# CS_16f1827.net
KiCad netlist of a schematic drawn in EAGLE
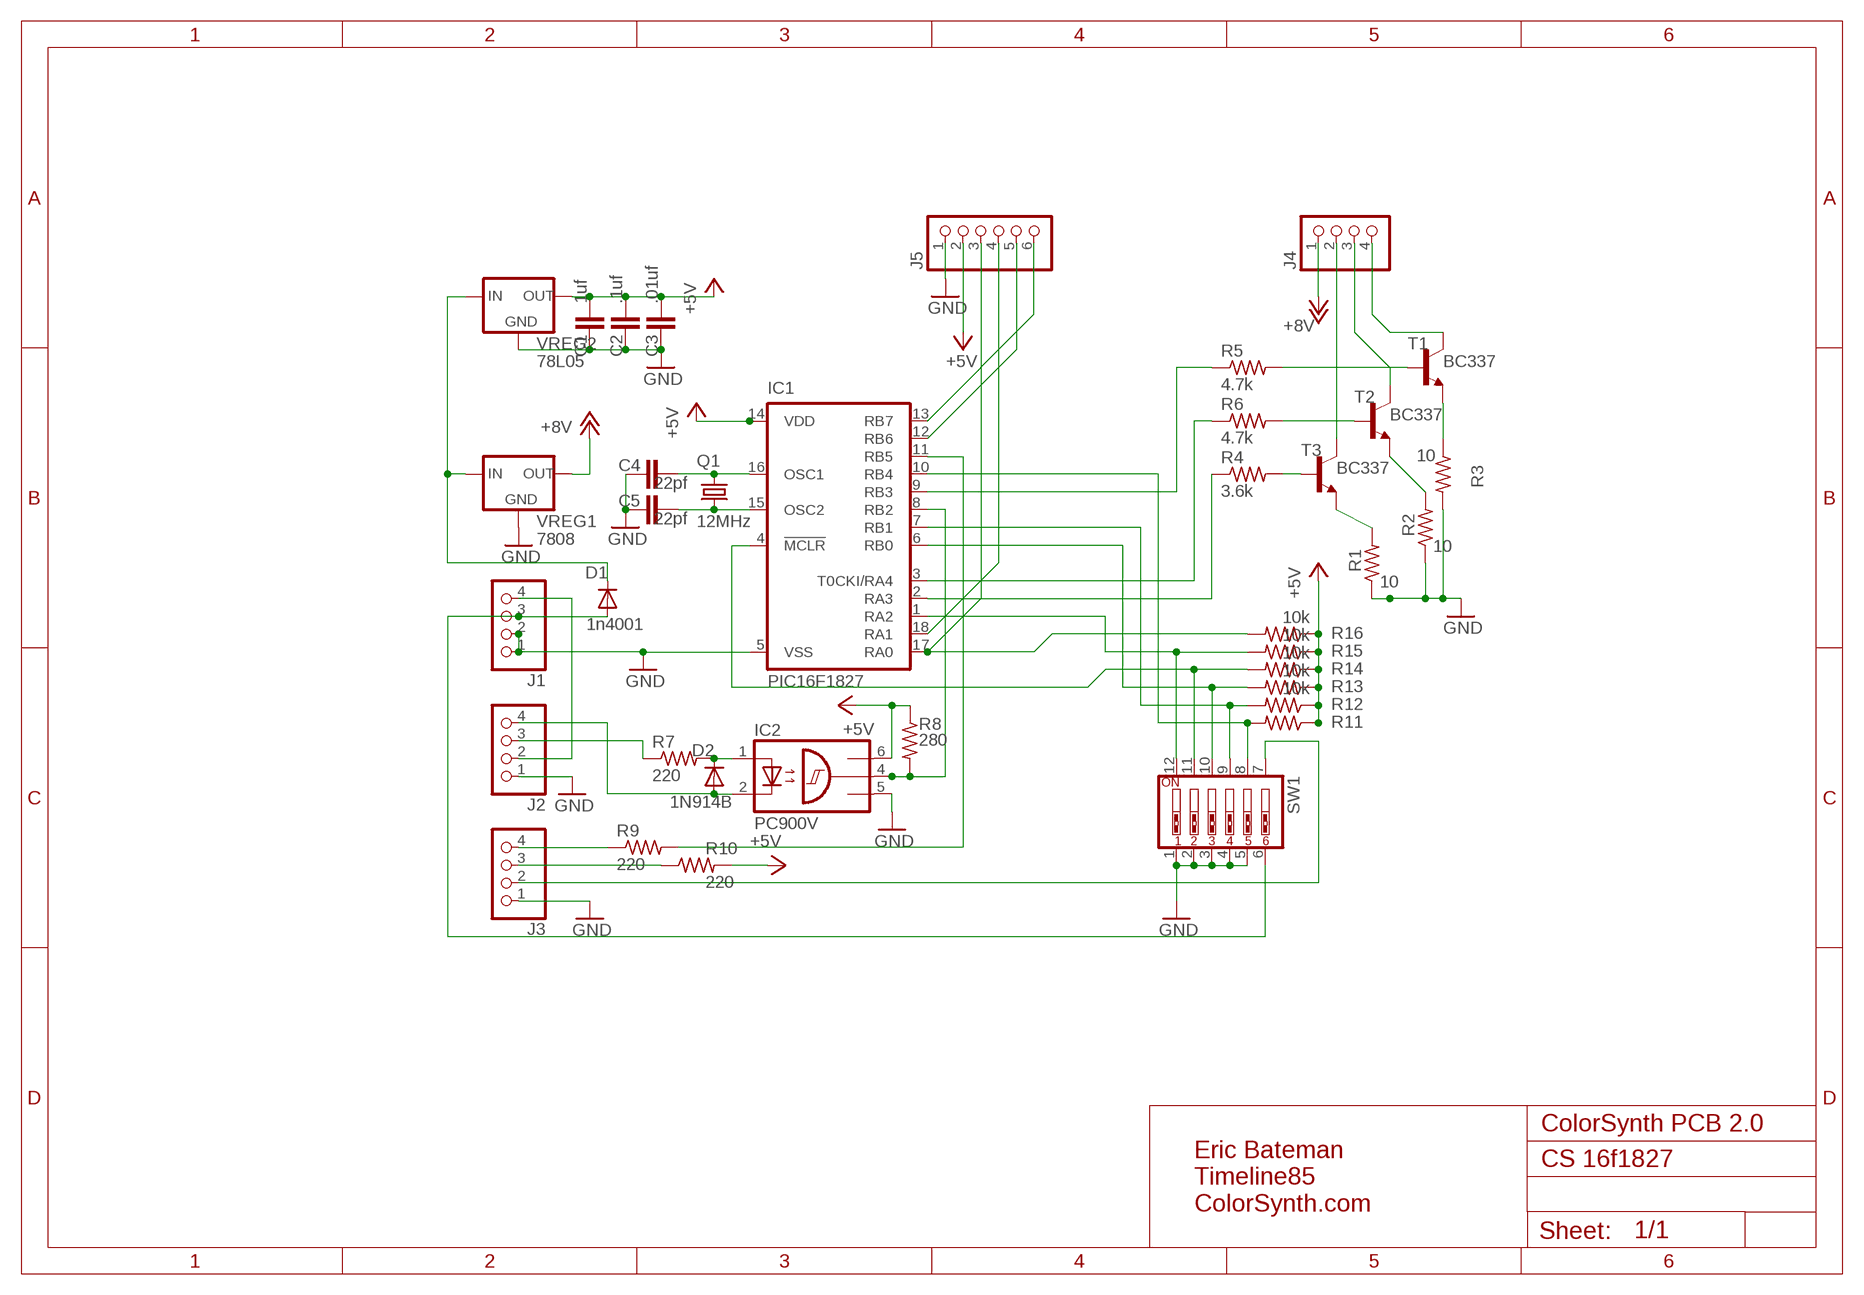
[diagram p0: schematic, sheet 1]

(export (version "E")
  (design (tool "Eeschema 10.0.6"))
  (components
    (comp (ref "C1")
      (value "1uf")
      (footprint "eagle-import:C5B3.5")
      (libsource (lib "eagle-import") (part "C5/3.5"))
    )
    (comp (ref "C2")
      (value ".1uf")
      (footprint "eagle-import:C5B3.5")
      (libsource (lib "eagle-import") (part "C5/3.5"))
    )
    (comp (ref "C3")
      (value ".01uf")
      (footprint "eagle-import:C5B3.5")
      (libsource (lib "eagle-import") (part "C5/3.5"))
    )
    (comp (ref "C4")
      (value "22pf")
      (footprint "eagle-import:C5B3.5")
      (libsource (lib "eagle-import") (part "C5/3.5"))
    )
    (comp (ref "C5")
      (value "22pf")
      (footprint "eagle-import:C5B3.5")
      (libsource (lib "eagle-import") (part "C5/3.5"))
    )
    (comp (ref "D1")
      (value "1n4001")
      (footprint "eagle-import:DO35-10")
      (libsource (lib "eagle-import") (part "1N4148DO35-10"))
    )
    (comp (ref "D2")
      (value "1N914B")
      (footprint "eagle-import:DO34-7")
      (libsource (lib "eagle-import") (part "BAS15"))
    )
    (comp (ref "IC1")
      (value "PIC16F1827")
      (footprint "eagle-import:DIL18")
      (libsource (lib "eagle-import") (part "PIC16F8P3"))
    )
    (comp (ref "IC2")
      (value "PC900V")
      (footprint "eagle-import:DIL06")
      (libsource (lib "eagle-import") (part "OPI8013"))
    )
    (comp (ref "J1")
      (value "PINHD-1X4")
      (footprint "eagle-import:1X04")
      (libsource (lib "eagle-import") (part "PINHD-1X4"))
    )
    (comp (ref "J2")
      (value "PINHD-1X4")
      (footprint "eagle-import:1X04")
      (libsource (lib "eagle-import") (part "PINHD-1X4"))
    )
    (comp (ref "J3")
      (value "PINHD-1X4")
      (footprint "eagle-import:1X04")
      (libsource (lib "eagle-import") (part "PINHD-1X4"))
    )
    (comp (ref "J4")
      (value "PINHD-1X4")
      (footprint "eagle-import:1X04")
      (libsource (lib "eagle-import") (part "PINHD-1X4"))
    )
    (comp (ref "J5")
      (value "PINHD-1X6")
      (footprint "eagle-import:1X06")
      (libsource (lib "eagle-import") (part "PINHD-1X6"))
    )
    (comp (ref "Q1")
      (value "12MHz")
      (footprint "eagle-import:HC49_S")
      (libsource (lib "eagle-import") (part "CRYSTALHC49S"))
    )
    (comp (ref "R1")
      (value "10")
      (footprint "eagle-import:0617V")
      (libsource (lib "eagle-import") (part "R-US_0617/5V"))
    )
    (comp (ref "R2")
      (value "10")
      (footprint "eagle-import:0617V")
      (libsource (lib "eagle-import") (part "R-US_0617/5V"))
    )
    (comp (ref "R3")
      (value "10")
      (footprint "eagle-import:0617V")
      (libsource (lib "eagle-import") (part "R-US_0617/5V"))
    )
    (comp (ref "R4")
      (value "3.6k")
      (footprint "eagle-import:0207_10")
      (libsource (lib "eagle-import") (part "R-US_0207/10"))
    )
    (comp (ref "R5")
      (value "4.7k")
      (footprint "eagle-import:0207_10")
      (libsource (lib "eagle-import") (part "R-US_0207/10"))
    )
    (comp (ref "R6")
      (value "4.7k")
      (footprint "eagle-import:0207_10")
      (libsource (lib "eagle-import") (part "R-US_0207/10"))
    )
    (comp (ref "R7")
      (value "220")
      (footprint "eagle-import:0207_10")
      (libsource (lib "eagle-import") (part "R-US_0207/10"))
    )
    (comp (ref "R8")
      (value "280")
      (footprint "eagle-import:0207_10")
      (libsource (lib "eagle-import") (part "R-US_0207/10"))
    )
    (comp (ref "R9")
      (value "220")
      (footprint "eagle-import:0207_10")
      (libsource (lib "eagle-import") (part "R-US_0207/10"))
    )
    (comp (ref "R10")
      (value "220")
      (footprint "eagle-import:0207_10")
      (libsource (lib "eagle-import") (part "R-US_0207/10"))
    )
    (comp (ref "R11")
      (value "10k")
      (footprint "eagle-import:0207_10")
      (libsource (lib "eagle-import") (part "R-US_0207/10"))
    )
    (comp (ref "R12")
      (value "10k")
      (footprint "eagle-import:0207_10")
      (libsource (lib "eagle-import") (part "R-US_0207/10"))
    )
    (comp (ref "R13")
      (value "10k")
      (footprint "eagle-import:0207_10")
      (libsource (lib "eagle-import") (part "R-US_0207/10"))
    )
    (comp (ref "R14")
      (value "10k")
      (footprint "eagle-import:0207_10")
      (libsource (lib "eagle-import") (part "R-US_0207/10"))
    )
    (comp (ref "R15")
      (value "10k")
      (footprint "eagle-import:0207_10")
      (libsource (lib "eagle-import") (part "R-US_0207/10"))
    )
    (comp (ref "R16")
      (value "10k")
      (footprint "eagle-import:0207_10")
      (libsource (lib "eagle-import") (part "R-US_0207/10"))
    )
    (comp (ref "SW1")
      (value "SW_DIP-6")
      (footprint "eagle-import:EDG-06")
      (libsource (lib "eagle-import") (part "SW_DIP-6"))
    )
    (comp (ref "T1")
      (value "BC337")
      (footprint "eagle-import:TO92-CBE")
      (libsource (lib "eagle-import") (part "BC337"))
    )
    (comp (ref "T2")
      (value "BC337")
      (footprint "eagle-import:TO92-CBE")
      (libsource (lib "eagle-import") (part "BC337"))
    )
    (comp (ref "T3")
      (value "BC337")
      (footprint "eagle-import:TO92-CBE")
      (libsource (lib "eagle-import") (part "BC337"))
    )
    (comp (ref "VREG1")
      (value "7808")
      (footprint "eagle-import:78XXS")
      (libsource (lib "eagle-import") (part "78XXS"))
    )
    (comp (ref "VREG2")
      (value "78L05")
      (footprint "eagle-import:78LXX")
      (libsource (lib "eagle-import") (part "78LXX"))
    )
  )
  (nets
    (net (code "1") (name "+5V") (class "Default")
      (node (ref "C1") (pin "1") (pinfunction "1_1") (pintype "passive"))
      (node (ref "C2") (pin "1") (pinfunction "1_1") (pintype "passive"))
      (node (ref "C3") (pin "1") (pinfunction "1_1") (pintype "passive"))
      (node (ref "IC1") (pin "14") (pinfunction "VDD_14") (pintype "power_in"))
      (node (ref "IC2") (pin "6") (pinfunction "VCC_6") (pintype "passive"))
      (node (ref "J5") (pin "2") (pinfunction "2_2") (pintype "passive"))
      (node (ref "R10") (pin "2") (pinfunction "2_2") (pintype "passive"))
      (node (ref "R11") (pin "1") (pinfunction "1_1") (pintype "passive"))
      (node (ref "R12") (pin "1") (pinfunction "1_1") (pintype "passive"))
      (node (ref "R13") (pin "1") (pinfunction "1_1") (pintype "passive"))
      (node (ref "R14") (pin "1") (pinfunction "1_1") (pintype "passive"))
      (node (ref "R15") (pin "1") (pinfunction "1_1") (pintype "passive"))
      (node (ref "R16") (pin "1") (pinfunction "1_1") (pintype "passive"))
      (node (ref "R8") (pin "1") (pinfunction "1_1") (pintype "passive"))
      (node (ref "VREG2") (pin "OUT") (pinfunction "OUT_OUT") (pintype "passive"))
    )
    (net (code "2") (name "+8V") (class "Default")
      (node (ref "J4") (pin "1") (pinfunction "1_1") (pintype "passive"))
      (node (ref "VREG1") (pin "OUT") (pinfunction "OUT_OUT") (pintype "passive"))
    )
    (net (code "3") (name "GND") (class "Default")
      (node (ref "C1") (pin "2") (pinfunction "2_2") (pintype "passive"))
      (node (ref "C2") (pin "2") (pinfunction "2_2") (pintype "passive"))
      (node (ref "C3") (pin "2") (pinfunction "2_2") (pintype "passive"))
      (node (ref "C4") (pin "2") (pinfunction "2_2") (pintype "passive"))
      (node (ref "C5") (pin "2") (pinfunction "2_2") (pintype "passive"))
      (node (ref "IC1") (pin "5") (pinfunction "VSS_5") (pintype "power_in"))
      (node (ref "IC2") (pin "5") (pinfunction "GND_5") (pintype "passive"))
      (node (ref "J1") (pin "1") (pinfunction "1_1") (pintype "passive"))
      (node (ref "J1") (pin "2") (pinfunction "2_2") (pintype "passive"))
      (node (ref "J2") (pin "1") (pinfunction "1_1") (pintype "passive"))
      (node (ref "J3") (pin "1") (pinfunction "1_1") (pintype "passive"))
      (node (ref "J5") (pin "1") (pinfunction "1_1") (pintype "passive"))
      (node (ref "R1") (pin "1") (pinfunction "1_1") (pintype "passive"))
      (node (ref "R2") (pin "1") (pinfunction "1_1") (pintype "passive"))
      (node (ref "R3") (pin "2") (pinfunction "2_2") (pintype "passive"))
      (node (ref "SW1") (pin "1") (pinfunction "1_1") (pintype "passive"))
      (node (ref "SW1") (pin "2") (pinfunction "2_2") (pintype "passive"))
      (node (ref "SW1") (pin "3") (pinfunction "3_3") (pintype "passive"))
      (node (ref "SW1") (pin "4") (pinfunction "4_4") (pintype "passive"))
      (node (ref "SW1") (pin "5") (pinfunction "5_5") (pintype "passive"))
      (node (ref "VREG1") (pin "GND") (pinfunction "GND_GND") (pintype "input"))
      (node (ref "VREG2") (pin "GND") (pinfunction "GND_GND") (pintype "input"))
    )
    (net (code "4") (name "Net-(D1-PadA)") (class "Default")
      (node (ref "D1") (pin "A") (pinfunction "A_A") (pintype "passive"))
      (node (ref "J1") (pin "3") (pinfunction "3_3") (pintype "passive"))
      (node (ref "SW1") (pin "6") (pinfunction "6_6") (pintype "passive"))
    )
    (net (code "5") (name "Net-(D1-PadC)") (class "Default")
      (node (ref "D1") (pin "C") (pinfunction "C_C") (pintype "passive"))
      (node (ref "VREG1") (pin "IN") (pinfunction "IN_IN") (pintype "input"))
      (node (ref "VREG2") (pin "IN") (pinfunction "IN_IN") (pintype "input"))
    )
    (net (code "6") (name "Net-(IC1-OSC1)") (class "Default")
      (node (ref "C4") (pin "1") (pinfunction "1_1") (pintype "passive"))
      (node (ref "IC1") (pin "16") (pinfunction "OSC1_16") (pintype "input"))
      (node (ref "Q1") (pin "1") (pinfunction "1_1") (pintype "passive"))
    )
    (net (code "7") (name "Net-(IC1-OSC2)") (class "Default")
      (node (ref "C5") (pin "1") (pinfunction "1_1") (pintype "passive"))
      (node (ref "IC1") (pin "15") (pinfunction "OSC2_15") (pintype "output"))
      (node (ref "Q1") (pin "2") (pinfunction "2_2") (pintype "passive"))
    )
    (net (code "8") (name "Net-(IC1-RA0)") (class "Default")
      (node (ref "IC1") (pin "17") (pinfunction "RA0_17") (pintype "bidirectional"))
      (node (ref "J5") (pin "3") (pinfunction "3_3") (pintype "passive"))
      (node (ref "R16") (pin "2") (pinfunction "2_2") (pintype "passive"))
    )
    (net (code "9") (name "Net-(IC1-RA1)") (class "Default")
      (node (ref "IC1") (pin "18") (pinfunction "RA1_18") (pintype "bidirectional"))
      (node (ref "J5") (pin "4") (pinfunction "4_4") (pintype "passive"))
    )
    (net (code "10") (name "Net-(IC1-RA2)") (class "Default")
      (node (ref "IC1") (pin "1") (pinfunction "RA2_1") (pintype "bidirectional"))
      (node (ref "R15") (pin "2") (pinfunction "2_2") (pintype "passive"))
      (node (ref "SW1") (pin "12") (pinfunction "12_12") (pintype "passive"))
    )
    (net (code "11") (name "Net-(IC1-RA3)") (class "Default")
      (node (ref "IC1") (pin "2") (pinfunction "RA3_2") (pintype "bidirectional"))
      (node (ref "R4") (pin "1") (pinfunction "1_1") (pintype "passive"))
    )
    (net (code "12") (name "Net-(IC1-RB0)") (class "Default")
      (node (ref "IC1") (pin "6") (pinfunction "RB0_6") (pintype "bidirectional"))
      (node (ref "R13") (pin "2") (pinfunction "2_2") (pintype "passive"))
      (node (ref "SW1") (pin "10") (pinfunction "10_10") (pintype "passive"))
    )
    (net (code "13") (name "Net-(IC1-RB1)") (class "Default")
      (node (ref "IC1") (pin "7") (pinfunction "RB1_7") (pintype "bidirectional"))
      (node (ref "R12") (pin "2") (pinfunction "2_2") (pintype "passive"))
      (node (ref "SW1") (pin "9") (pinfunction "9_9") (pintype "passive"))
    )
    (net (code "14") (name "Net-(IC1-RB2)") (class "Default")
      (node (ref "IC1") (pin "8") (pinfunction "RB2_8") (pintype "bidirectional"))
      (node (ref "IC2") (pin "4") (pinfunction "OUT_4") (pintype "passive"))
      (node (ref "R8") (pin "2") (pinfunction "2_2") (pintype "passive"))
    )
    (net (code "15") (name "Net-(IC1-RB3)") (class "Default")
      (node (ref "IC1") (pin "9") (pinfunction "RB3_9") (pintype "bidirectional"))
      (node (ref "R5") (pin "1") (pinfunction "1_1") (pintype "passive"))
    )
    (net (code "16") (name "Net-(IC1-RB4)") (class "Default")
      (node (ref "IC1") (pin "10") (pinfunction "RB4_10") (pintype "bidirectional"))
      (node (ref "R11") (pin "2") (pinfunction "2_2") (pintype "passive"))
      (node (ref "SW1") (pin "8") (pinfunction "8_8") (pintype "passive"))
    )
    (net (code "17") (name "Net-(IC1-RB5)") (class "Default")
      (node (ref "IC1") (pin "11") (pinfunction "RB5_11") (pintype "bidirectional"))
      (node (ref "R9") (pin "2") (pinfunction "2_2") (pintype "passive"))
    )
    (net (code "18") (name "Net-(IC1-RB6)") (class "Default")
      (node (ref "IC1") (pin "12") (pinfunction "RB6_12") (pintype "bidirectional"))
      (node (ref "J5") (pin "5") (pinfunction "5_5") (pintype "passive"))
    )
    (net (code "19") (name "Net-(IC1-RB7)") (class "Default")
      (node (ref "IC1") (pin "13") (pinfunction "RB7_13") (pintype "bidirectional"))
      (node (ref "J5") (pin "6") (pinfunction "6_6") (pintype "passive"))
    )
    (net (code "20") (name "Net-(IC1-T0CKI{slash}RA4)") (class "Default")
      (node (ref "IC1") (pin "3") (pinfunction "T0CKI/RA4_3") (pintype "bidirectional"))
      (node (ref "R6") (pin "1") (pinfunction "1_1") (pintype "passive"))
    )
    (net (code "21") (name "Net-(IC1-~{MCLR})") (class "Default")
      (node (ref "IC1") (pin "4") (pinfunction "~{MCLR}_4") (pintype "input"))
      (node (ref "R14") (pin "2") (pinfunction "2_2") (pintype "passive"))
      (node (ref "SW1") (pin "11") (pinfunction "11_11") (pintype "passive"))
    )
    (net (code "22") (name "Net-(IC2-A)") (class "Default")
      (node (ref "D2") (pin "C") (pinfunction "C_C") (pintype "passive"))
      (node (ref "IC2") (pin "1") (pinfunction "A_1") (pintype "passive"))
      (node (ref "R7") (pin "2") (pinfunction "2_2") (pintype "passive"))
    )
    (net (code "23") (name "Net-(IC2-C)") (class "Default")
      (node (ref "D2") (pin "A") (pinfunction "A_A") (pintype "passive"))
      (node (ref "IC2") (pin "2") (pinfunction "C_2") (pintype "passive"))
      (node (ref "J2") (pin "4") (pinfunction "4_4") (pintype "passive"))
    )
    (net (code "24") (name "Net-(J1-Pad4)") (class "Default")
      (node (ref "J1") (pin "4") (pinfunction "4_4") (pintype "passive"))
      (node (ref "J2") (pin "2") (pinfunction "2_2") (pintype "passive"))
    )
    (net (code "25") (name "Net-(J2-Pad3)") (class "Default")
      (node (ref "J2") (pin "3") (pinfunction "3_3") (pintype "passive"))
      (node (ref "R7") (pin "1") (pinfunction "1_1") (pintype "passive"))
    )
    (net (code "26") (name "Net-(J3-Pad2)") (class "Default")
      (node (ref "J3") (pin "2") (pinfunction "2_2") (pintype "passive"))
      (node (ref "SW1") (pin "7") (pinfunction "7_7") (pintype "passive"))
    )
    (net (code "27") (name "Net-(J3-Pad3)") (class "Default")
      (node (ref "J3") (pin "3") (pinfunction "3_3") (pintype "passive"))
      (node (ref "R10") (pin "1") (pinfunction "1_1") (pintype "passive"))
    )
    (net (code "28") (name "Net-(J3-Pad4)") (class "Default")
      (node (ref "J3") (pin "4") (pinfunction "4_4") (pintype "passive"))
      (node (ref "R9") (pin "1") (pinfunction "1_1") (pintype "passive"))
    )
    (net (code "29") (name "Net-(J4-Pad2)") (class "Default")
      (node (ref "J4") (pin "2") (pinfunction "2_2") (pintype "passive"))
      (node (ref "T3") (pin "C") (pinfunction "C_C") (pintype "passive"))
    )
    (net (code "30") (name "Net-(J4-Pad3)") (class "Default")
      (node (ref "J4") (pin "3") (pinfunction "3_3") (pintype "passive"))
      (node (ref "T2") (pin "C") (pinfunction "C_C") (pintype "passive"))
    )
    (net (code "31") (name "Net-(J4-Pad4)") (class "Default")
      (node (ref "J4") (pin "4") (pinfunction "4_4") (pintype "passive"))
      (node (ref "T1") (pin "C") (pinfunction "C_C") (pintype "passive"))
    )
    (net (code "32") (name "Net-(R1-Pad2)") (class "Default")
      (node (ref "R1") (pin "2") (pinfunction "2_2") (pintype "passive"))
      (node (ref "T3") (pin "E") (pinfunction "E_E") (pintype "passive"))
    )
    (net (code "33") (name "Net-(R2-Pad2)") (class "Default")
      (node (ref "R2") (pin "2") (pinfunction "2_2") (pintype "passive"))
      (node (ref "T2") (pin "E") (pinfunction "E_E") (pintype "passive"))
    )
    (net (code "34") (name "Net-(R3-Pad1)") (class "Default")
      (node (ref "R3") (pin "1") (pinfunction "1_1") (pintype "passive"))
      (node (ref "T1") (pin "E") (pinfunction "E_E") (pintype "passive"))
    )
    (net (code "35") (name "Net-(R4-Pad2)") (class "Default")
      (node (ref "R4") (pin "2") (pinfunction "2_2") (pintype "passive"))
      (node (ref "T3") (pin "B") (pinfunction "B_B") (pintype "passive"))
    )
    (net (code "36") (name "Net-(R5-Pad2)") (class "Default")
      (node (ref "R5") (pin "2") (pinfunction "2_2") (pintype "passive"))
      (node (ref "T1") (pin "B") (pinfunction "B_B") (pintype "passive"))
    )
    (net (code "37") (name "Net-(R6-Pad2)") (class "Default")
      (node (ref "R6") (pin "2") (pinfunction "2_2") (pintype "passive"))
      (node (ref "T2") (pin "B") (pinfunction "B_B") (pintype "passive"))
    )
  )
)
